# jmb575.net
KiCad netlist of a schematic drawn in Altium Designer
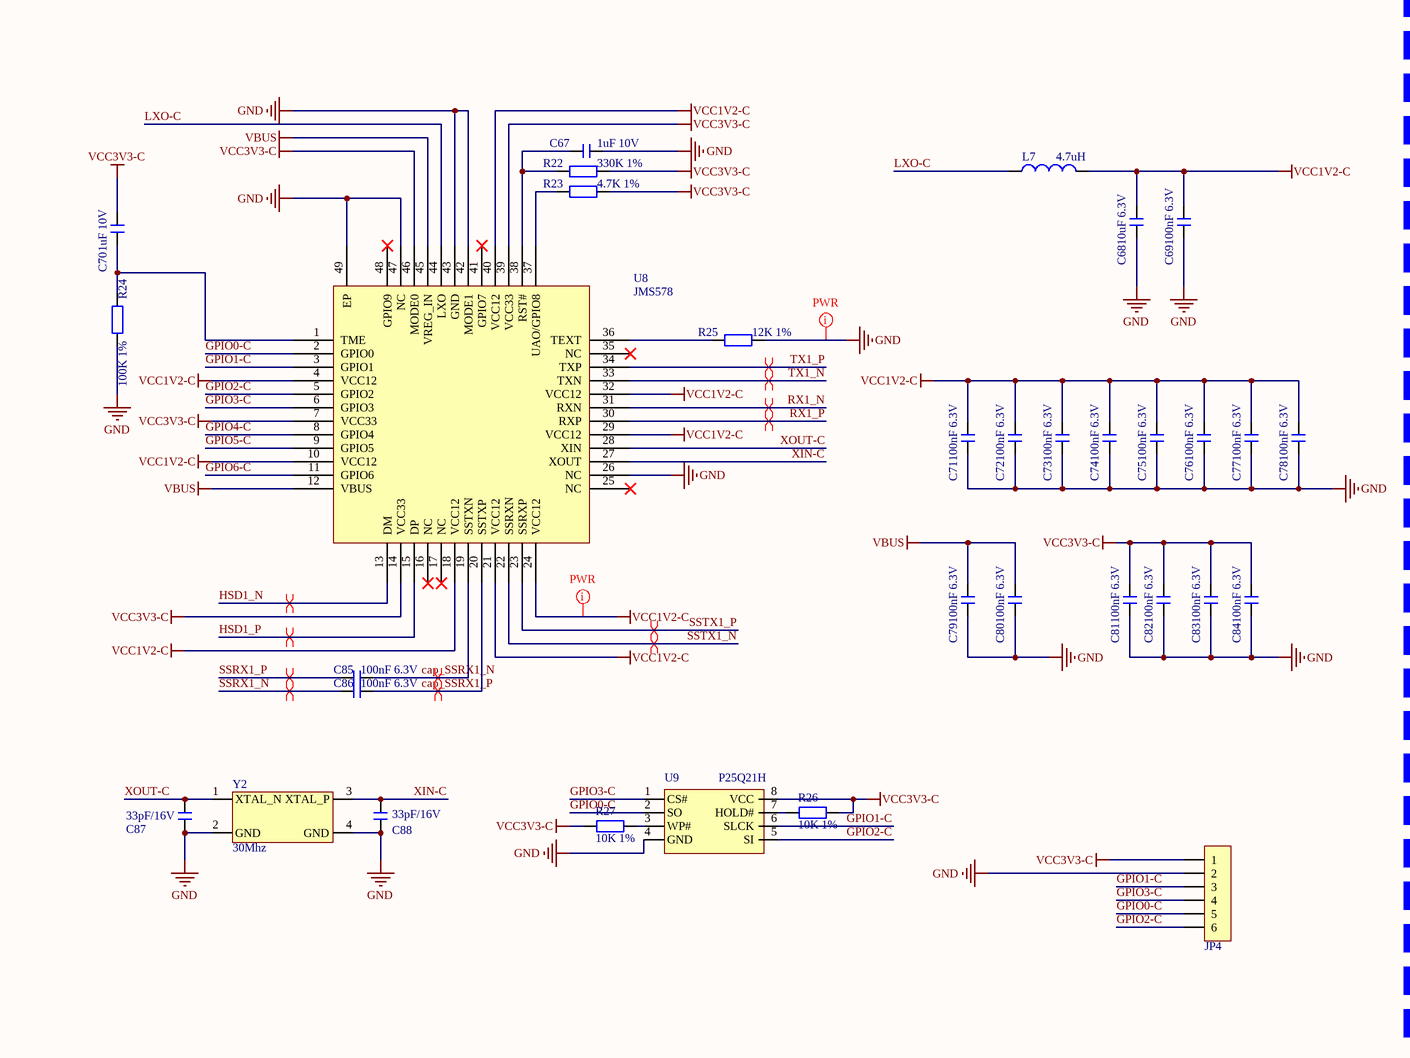
[diagram p0: jmb575.SchDoc, left]
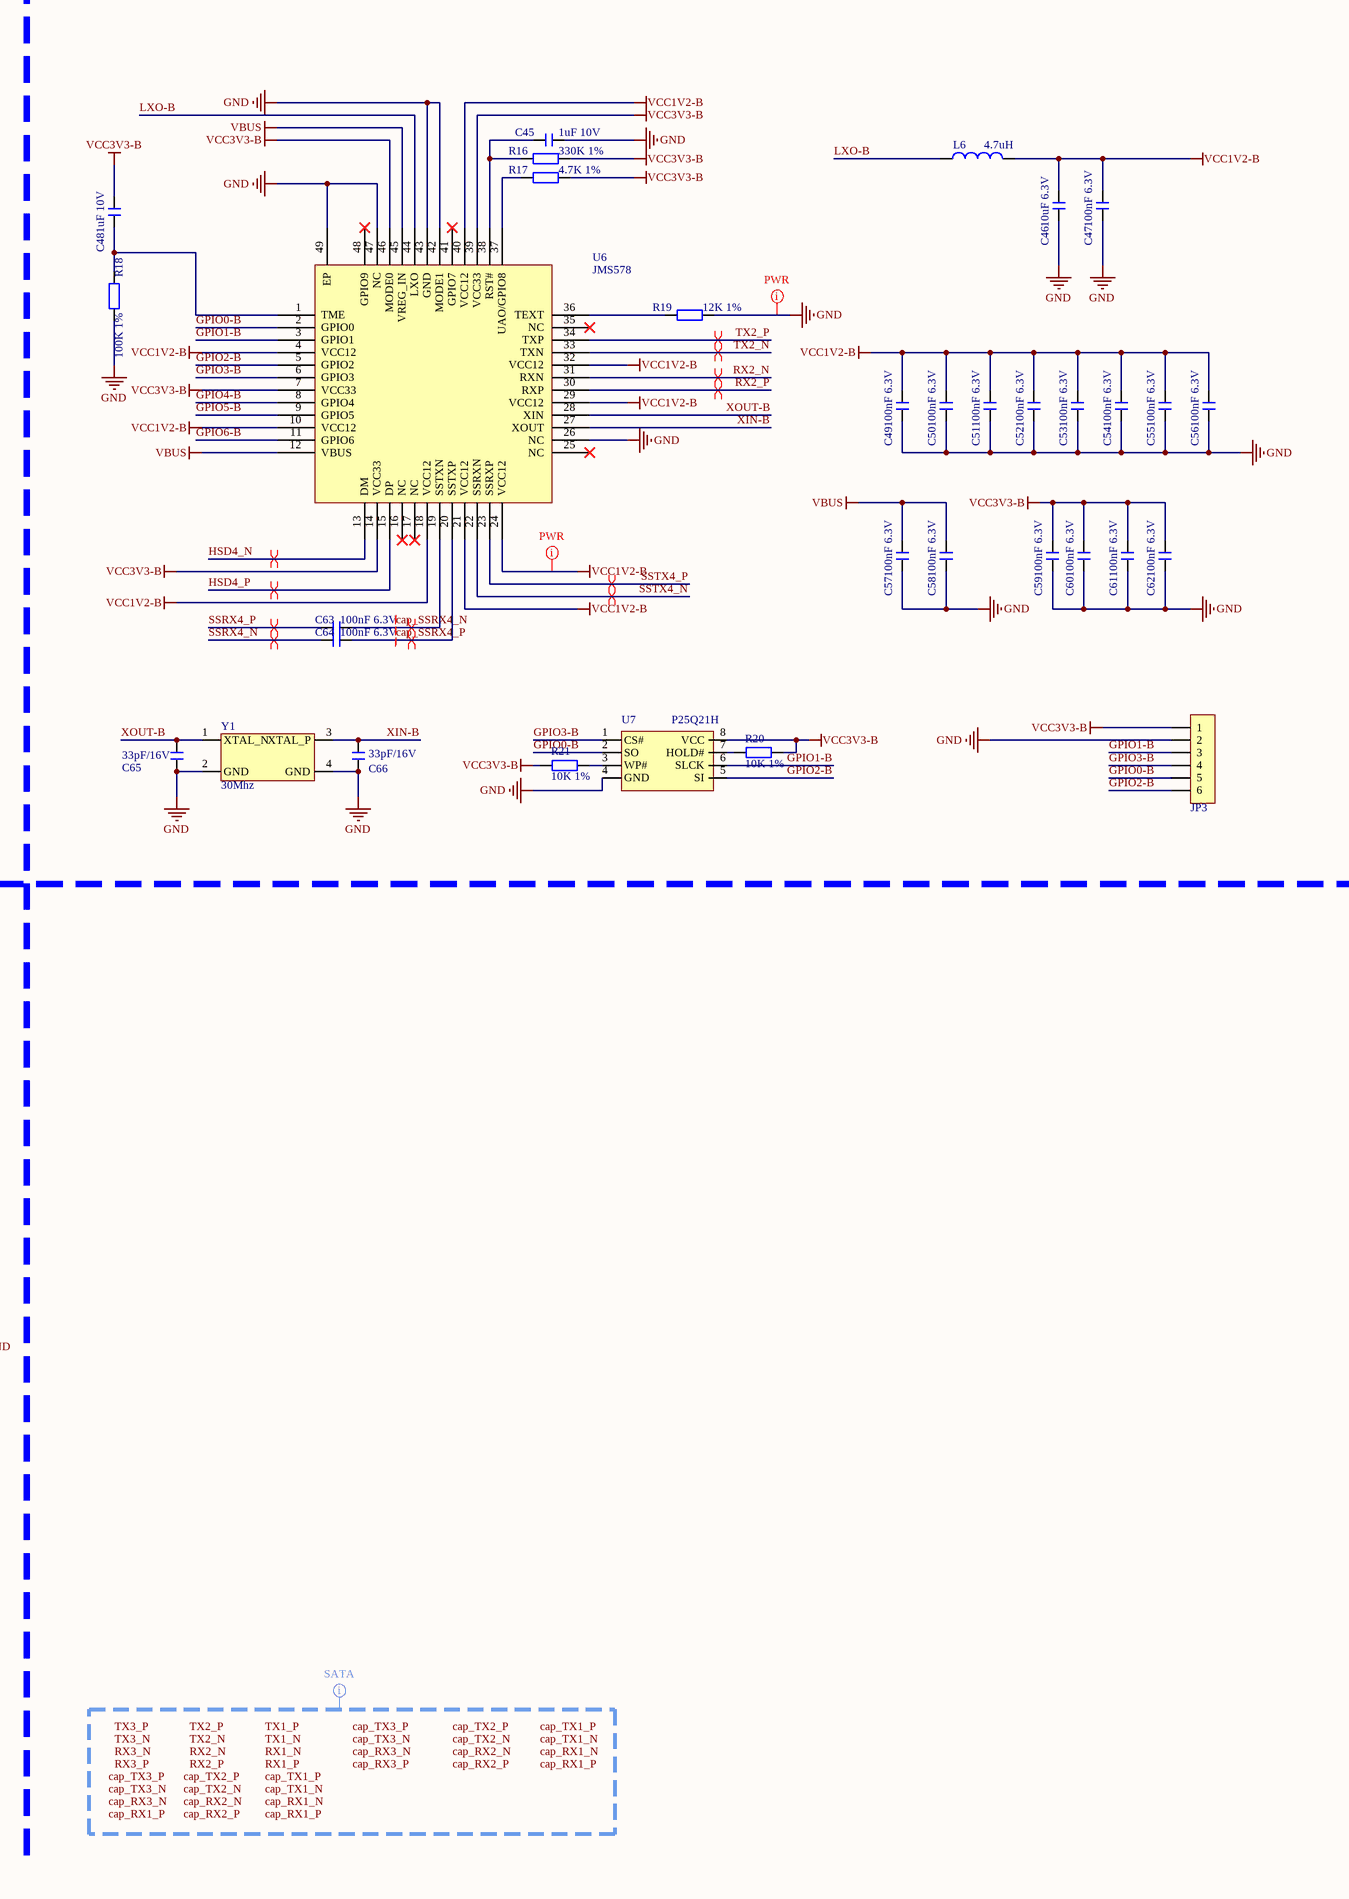
[diagram p1: jmb575.SchDoc, right]

(export (version "E")
  (design (tool "Eeschema 10.0.6"))
  (components
    (comp (ref "C45")
      (value "1uF 10V")
      (footprint "C0402_L")
      (description "无极性贴片电容")
      (fields (field (name "版权归属") "源创客"))
      (libsource (lib "Capacitor") (part "C"))
    )
    (comp (ref "C46")
      (value "10uF 6.3V")
      (footprint "C0603_L")
      (description "无极性贴片电容")
      (fields (field (name "版权归属") "源创客"))
      (libsource (lib "Capacitor") (part "C"))
    )
    (comp (ref "C47")
      (value "100nF 6.3V")
      (footprint "C0402_L")
      (description "无极性贴片电容")
      (fields (field (name "版权归属") "源创客"))
      (libsource (lib "Capacitor") (part "C"))
    )
    (comp (ref "C48")
      (value "1uF 10V")
      (footprint "C0402_L")
      (description "无极性贴片电容")
      (fields (field (name "版权归属") "源创客"))
      (libsource (lib "Capacitor") (part "C"))
    )
    (comp (ref "C49")
      (value "100nF 6.3V")
      (footprint "C0402_L")
      (description "无极性贴片电容")
      (fields (field (name "版权归属") "源创客"))
      (libsource (lib "Capacitor") (part "C"))
    )
    (comp (ref "C50")
      (value "100nF 6.3V")
      (footprint "C0402_L")
      (description "无极性贴片电容")
      (fields (field (name "版权归属") "源创客"))
      (libsource (lib "Capacitor") (part "C"))
    )
    (comp (ref "C51")
      (value "100nF 6.3V")
      (footprint "C0402_L")
      (description "无极性贴片电容")
      (fields (field (name "版权归属") "源创客"))
      (libsource (lib "Capacitor") (part "C"))
    )
    (comp (ref "C52")
      (value "100nF 6.3V")
      (footprint "C0402_L")
      (description "无极性贴片电容")
      (fields (field (name "版权归属") "源创客"))
      (libsource (lib "Capacitor") (part "C"))
    )
    (comp (ref "C53")
      (value "100nF 6.3V")
      (footprint "C0402_L")
      (description "无极性贴片电容")
      (fields (field (name "版权归属") "源创客"))
      (libsource (lib "Capacitor") (part "C"))
    )
    (comp (ref "C54")
      (value "100nF 6.3V")
      (footprint "C0402_L")
      (description "无极性贴片电容")
      (fields (field (name "版权归属") "源创客"))
      (libsource (lib "Capacitor") (part "C"))
    )
    (comp (ref "C55")
      (value "100nF 6.3V")
      (footprint "C0402_L")
      (description "无极性贴片电容")
      (fields (field (name "版权归属") "源创客"))
      (libsource (lib "Capacitor") (part "C"))
    )
    (comp (ref "C56")
      (value "100nF 6.3V")
      (footprint "C0402_L")
      (description "无极性贴片电容")
      (fields (field (name "版权归属") "源创客"))
      (libsource (lib "Capacitor") (part "C"))
    )
    (comp (ref "C57")
      (value "100nF 6.3V")
      (footprint "C0402_L")
      (description "无极性贴片电容")
      (fields (field (name "版权归属") "源创客"))
      (libsource (lib "Capacitor") (part "C"))
    )
    (comp (ref "C58")
      (value "100nF 6.3V")
      (footprint "C0402_L")
      (description "无极性贴片电容")
      (fields (field (name "版权归属") "源创客"))
      (libsource (lib "Capacitor") (part "C"))
    )
    (comp (ref "C59")
      (value "100nF 6.3V")
      (footprint "C0402_L")
      (description "无极性贴片电容")
      (fields (field (name "版权归属") "源创客"))
      (libsource (lib "Capacitor") (part "C"))
    )
    (comp (ref "C60")
      (value "100nF 6.3V")
      (footprint "C0402_L")
      (description "无极性贴片电容")
      (fields (field (name "版权归属") "源创客"))
      (libsource (lib "Capacitor") (part "C"))
    )
    (comp (ref "C61")
      (value "100nF 6.3V")
      (footprint "C0402_L")
      (description "无极性贴片电容")
      (fields (field (name "版权归属") "源创客"))
      (libsource (lib "Capacitor") (part "C"))
    )
    (comp (ref "C62")
      (value "100nF 6.3V")
      (footprint "C0402_L")
      (description "无极性贴片电容")
      (fields (field (name "版权归属") "源创客"))
      (libsource (lib "Capacitor") (part "C"))
    )
    (comp (ref "C63")
      (value "100nF 6.3V")
      (footprint "C0402_L")
      (description "无极性贴片电容")
      (fields (field (name "版权归属") "源创客"))
      (libsource (lib "Capacitor") (part "C"))
    )
    (comp (ref "C64")
      (value "100nF 6.3V")
      (footprint "C0402_L")
      (description "无极性贴片电容")
      (fields (field (name "版权归属") "源创客"))
      (libsource (lib "Capacitor") (part "C"))
    )
    (comp (ref "C65")
      (value "33pF/16V")
      (footprint "C0402_L")
      (description "无极性贴片电容")
      (fields (field (name "版权归属") "源创客"))
      (libsource (lib "Capacitor") (part "C"))
    )
    (comp (ref "C66")
      (value "33pF/16V")
      (footprint "C0402_L")
      (description "无极性贴片电容")
      (fields (field (name "版权归属") "源创客"))
      (libsource (lib "Capacitor") (part "C"))
    )
    (comp (ref "C67")
      (value "1uF 10V")
      (footprint "C0402_L")
      (description "无极性贴片电容")
      (fields (field (name "版权归属") "源创客"))
      (libsource (lib "Capacitor") (part "C"))
    )
    (comp (ref "C68")
      (value "10uF 6.3V")
      (footprint "C0603_L")
      (description "无极性贴片电容")
      (fields (field (name "版权归属") "源创客"))
      (libsource (lib "Capacitor") (part "C"))
    )
    (comp (ref "C69")
      (value "100nF 6.3V")
      (footprint "C0402_L")
      (description "无极性贴片电容")
      (fields (field (name "版权归属") "源创客"))
      (libsource (lib "Capacitor") (part "C"))
    )
    (comp (ref "C70")
      (value "1uF 10V")
      (footprint "C0402_L")
      (description "无极性贴片电容")
      (fields (field (name "版权归属") "源创客"))
      (libsource (lib "Capacitor") (part "C"))
    )
    (comp (ref "C71")
      (value "100nF 6.3V")
      (footprint "C0402_L")
      (description "无极性贴片电容")
      (fields (field (name "版权归属") "源创客"))
      (libsource (lib "Capacitor") (part "C"))
    )
    (comp (ref "C72")
      (value "100nF 6.3V")
      (footprint "C0402_L")
      (description "无极性贴片电容")
      (fields (field (name "版权归属") "源创客"))
      (libsource (lib "Capacitor") (part "C"))
    )
    (comp (ref "C73")
      (value "100nF 6.3V")
      (footprint "C0402_L")
      (description "无极性贴片电容")
      (fields (field (name "版权归属") "源创客"))
      (libsource (lib "Capacitor") (part "C"))
    )
    (comp (ref "C74")
      (value "100nF 6.3V")
      (footprint "C0402_L")
      (description "无极性贴片电容")
      (fields (field (name "版权归属") "源创客"))
      (libsource (lib "Capacitor") (part "C"))
    )
    (comp (ref "C75")
      (value "100nF 6.3V")
      (footprint "C0402_L")
      (description "无极性贴片电容")
      (fields (field (name "版权归属") "源创客"))
      (libsource (lib "Capacitor") (part "C"))
    )
    (comp (ref "C76")
      (value "100nF 6.3V")
      (footprint "C0402_L")
      (description "无极性贴片电容")
      (fields (field (name "版权归属") "源创客"))
      (libsource (lib "Capacitor") (part "C"))
    )
    (comp (ref "C77")
      (value "100nF 6.3V")
      (footprint "C0402_L")
      (description "无极性贴片电容")
      (fields (field (name "版权归属") "源创客"))
      (libsource (lib "Capacitor") (part "C"))
    )
    (comp (ref "C78")
      (value "100nF 6.3V")
      (footprint "C0402_L")
      (description "无极性贴片电容")
      (fields (field (name "版权归属") "源创客"))
      (libsource (lib "Capacitor") (part "C"))
    )
    (comp (ref "C79")
      (value "100nF 6.3V")
      (footprint "C0402_L")
      (description "无极性贴片电容")
      (fields (field (name "版权归属") "源创客"))
      (libsource (lib "Capacitor") (part "C"))
    )
    (comp (ref "C80")
      (value "100nF 6.3V")
      (footprint "C0402_L")
      (description "无极性贴片电容")
      (fields (field (name "版权归属") "源创客"))
      (libsource (lib "Capacitor") (part "C"))
    )
    (comp (ref "C81")
      (value "100nF 6.3V")
      (footprint "C0402_L")
      (description "无极性贴片电容")
      (fields (field (name "版权归属") "源创客"))
      (libsource (lib "Capacitor") (part "C"))
    )
    (comp (ref "C82")
      (value "100nF 6.3V")
      (footprint "C0402_L")
      (description "无极性贴片电容")
      (fields (field (name "版权归属") "源创客"))
      (libsource (lib "Capacitor") (part "C"))
    )
    (comp (ref "C83")
      (value "100nF 6.3V")
      (footprint "C0402_L")
      (description "无极性贴片电容")
      (fields (field (name "版权归属") "源创客"))
      (libsource (lib "Capacitor") (part "C"))
    )
    (comp (ref "C84")
      (value "100nF 6.3V")
      (footprint "C0402_L")
      (description "无极性贴片电容")
      (fields (field (name "版权归属") "源创客"))
      (libsource (lib "Capacitor") (part "C"))
    )
    (comp (ref "C85")
      (value "100nF 6.3V")
      (footprint "C0402_L")
      (description "无极性贴片电容")
      (fields (field (name "版权归属") "源创客"))
      (libsource (lib "Capacitor") (part "C"))
    )
    (comp (ref "C86")
      (value "100nF 6.3V")
      (footprint "C0402_L")
      (description "无极性贴片电容")
      (fields (field (name "版权归属") "源创客"))
      (libsource (lib "Capacitor") (part "C"))
    )
    (comp (ref "C87")
      (value "33pF/16V")
      (footprint "C0402_L")
      (description "无极性贴片电容")
      (fields (field (name "版权归属") "源创客"))
      (libsource (lib "Capacitor") (part "C"))
    )
    (comp (ref "C88")
      (value "33pF/16V")
      (footprint "C0402_L")
      (description "无极性贴片电容")
      (fields (field (name "版权归属") "源创客"))
      (libsource (lib "Capacitor") (part "C"))
    )
    (comp (ref "JP3")
      (value "HDR-1X6")
      (footprint "6p烧录点")
      (description "6P接插件")
      (fields (field (name "版权归属") "源创客"))
      (libsource (lib "Connector-PinHeader") (part "Header 6"))
    )
    (comp (ref "JP4")
      (value "HDR-1X6")
      (footprint "6p烧录点")
      (description "6P接插件")
      (fields (field (name "版权归属") "源创客"))
      (libsource (lib "Connector-PinHeader") (part "Header 6"))
    )
    (comp (ref "L6")
      (value "4.7uH")
      (footprint "SMMS0420")
      (description "小功率贴片电感")
      (fields (field (name "版权归属") "源创客"))
      (libsource (lib "Inductor") (part "L"))
    )
    (comp (ref "L7")
      (value "4.7uH")
      (footprint "SMMS0420")
      (description "小功率贴片电感")
      (fields (field (name "版权归属") "源创客"))
      (libsource (lib "Inductor") (part "L"))
    )
    (comp (ref "R16")
      (value "330K 1%")
      (footprint "R0402_L")
      (description "贴片电阻")
      (fields (field (name "版权归属") "源创客"))
      (libsource (lib "Resistor") (part "R"))
    )
    (comp (ref "R17")
      (value "4.7K 1%")
      (footprint "R0402_L")
      (description "贴片电阻")
      (fields (field (name "版权归属") "源创客"))
      (libsource (lib "Resistor") (part "R"))
    )
    (comp (ref "R18")
      (value "100K 1%")
      (footprint "R0402_L")
      (description "贴片电阻")
      (fields (field (name "版权归属") "源创客"))
      (libsource (lib "Resistor") (part "R"))
    )
    (comp (ref "R19")
      (value "12K 1%")
      (footprint "R0402_L")
      (description "贴片电阻")
      (fields (field (name "版权归属") "源创客"))
      (libsource (lib "Resistor") (part "R"))
    )
    (comp (ref "R20")
      (value "10K 1%")
      (footprint "R0402_L")
      (description "贴片电阻")
      (fields (field (name "版权归属") "源创客"))
      (libsource (lib "Resistor") (part "R"))
    )
    (comp (ref "R21")
      (value "10K 1%")
      (footprint "R0402_L")
      (description "贴片电阻")
      (fields (field (name "版权归属") "源创客"))
      (libsource (lib "Resistor") (part "R"))
    )
    (comp (ref "R22")
      (value "330K 1%")
      (footprint "R0402_L")
      (description "贴片电阻")
      (fields (field (name "版权归属") "源创客"))
      (libsource (lib "Resistor") (part "R"))
    )
    (comp (ref "R23")
      (value "4.7K 1%")
      (footprint "R0402_L")
      (description "贴片电阻")
      (fields (field (name "版权归属") "源创客"))
      (libsource (lib "Resistor") (part "R"))
    )
    (comp (ref "R24")
      (value "100K 1%")
      (footprint "R0402_L")
      (description "贴片电阻")
      (fields (field (name "版权归属") "源创客"))
      (libsource (lib "Resistor") (part "R"))
    )
    (comp (ref "R25")
      (value "12K 1%")
      (footprint "R0402_L")
      (description "贴片电阻")
      (fields (field (name "版权归属") "源创客"))
      (libsource (lib "Resistor") (part "R"))
    )
    (comp (ref "R26")
      (value "10K 1%")
      (footprint "R0402_L")
      (description "贴片电阻")
      (fields (field (name "版权归属") "源创客"))
      (libsource (lib "Resistor") (part "R"))
    )
    (comp (ref "R27")
      (value "10K 1%")
      (footprint "R0402_L")
      (description "贴片电阻")
      (fields (field (name "版权归属") "源创客"))
      (libsource (lib "Resistor") (part "R"))
    )
    (comp (ref "U6")
      (value "JMS578")
      (footprint "QFN48-L6.0-W6.0-P0.4")
      (libsource (lib "Brage") (part "JMS578"))
    )
    (comp (ref "U7") (value "P25Q21H") (footprint "SOP8_L") (libsource (lib "Flash") (part "P25D40H")))
    (comp (ref "U8")
      (value "JMS578")
      (footprint "QFN48-L6.0-W6.0-P0.4")
      (libsource (lib "Brage") (part "JMS578"))
    )
    (comp (ref "U9") (value "P25Q21H") (footprint "SOP8_L") (libsource (lib "Flash") (part "P25D40H")))
    (comp (ref "Y1") (value "30Mhz") (footprint "OSC 3225-4P") (libsource (lib "Crystal") (part "Crystal")))
    (comp (ref "Y2") (value "30Mhz") (footprint "OSC 3225-4P") (libsource (lib "Crystal") (part "Crystal")))
  )
  (nets
    (net (code "1") (name "/GPIO0-B") (class "Default")
      (node (ref "JP3") (pin "5") (pinfunction "5_5") (pintype "passive"))
      (node (ref "U6") (pin "2") (pinfunction "GPIO0_2") (pintype "passive"))
      (node (ref "U7") (pin "2") (pinfunction "SO_2") (pintype "passive"))
    )
    (net (code "2") (name "/GPIO0-C") (class "Default")
      (node (ref "JP4") (pin "5") (pinfunction "5_5") (pintype "passive"))
      (node (ref "U8") (pin "2") (pinfunction "GPIO0_2") (pintype "passive"))
      (node (ref "U9") (pin "2") (pinfunction "SO_2") (pintype "passive"))
    )
    (net (code "3") (name "/GPIO1-B") (class "Default")
      (node (ref "JP3") (pin "3") (pinfunction "3_3") (pintype "passive"))
      (node (ref "U6") (pin "3") (pinfunction "GPIO1_3") (pintype "passive"))
      (node (ref "U7") (pin "6") (pinfunction "SLCK_6") (pintype "passive"))
    )
    (net (code "4") (name "/GPIO1-C") (class "Default")
      (node (ref "JP4") (pin "3") (pinfunction "3_3") (pintype "passive"))
      (node (ref "U8") (pin "3") (pinfunction "GPIO1_3") (pintype "passive"))
      (node (ref "U9") (pin "6") (pinfunction "SLCK_6") (pintype "passive"))
    )
    (net (code "5") (name "/GPIO2-B") (class "Default")
      (node (ref "JP3") (pin "6") (pinfunction "6_6") (pintype "passive"))
      (node (ref "U6") (pin "5") (pinfunction "GPIO2_5") (pintype "passive"))
      (node (ref "U7") (pin "5") (pinfunction "SI_5") (pintype "passive"))
    )
    (net (code "6") (name "/GPIO2-C") (class "Default")
      (node (ref "JP4") (pin "6") (pinfunction "6_6") (pintype "passive"))
      (node (ref "U8") (pin "5") (pinfunction "GPIO2_5") (pintype "passive"))
      (node (ref "U9") (pin "5") (pinfunction "SI_5") (pintype "passive"))
    )
    (net (code "7") (name "/GPIO3-B") (class "Default")
      (node (ref "JP3") (pin "4") (pinfunction "4_4") (pintype "passive"))
      (node (ref "U6") (pin "6") (pinfunction "GPIO3_6") (pintype "passive"))
      (node (ref "U7") (pin "1") (pinfunction "CS#_1") (pintype "passive"))
    )
    (net (code "8") (name "/GPIO3-C") (class "Default")
      (node (ref "JP4") (pin "4") (pinfunction "4_4") (pintype "passive"))
      (node (ref "U8") (pin "6") (pinfunction "GPIO3_6") (pintype "passive"))
      (node (ref "U9") (pin "1") (pinfunction "CS#_1") (pintype "passive"))
    )
    (net (code "9") (name "/GPIO4-B") (class "Default")
      (node (ref "U6") (pin "8") (pinfunction "GPIO4_8") (pintype "passive"))
    )
    (net (code "10") (name "/GPIO4-C") (class "Default")
      (node (ref "U8") (pin "8") (pinfunction "GPIO4_8") (pintype "passive"))
    )
    (net (code "11") (name "/GPIO5-B") (class "Default")
      (node (ref "U6") (pin "9") (pinfunction "GPIO5_9") (pintype "passive"))
    )
    (net (code "12") (name "/GPIO5-C") (class "Default")
      (node (ref "U8") (pin "9") (pinfunction "GPIO5_9") (pintype "passive"))
    )
    (net (code "13") (name "/GPIO6-B") (class "Default")
      (node (ref "U6") (pin "11") (pinfunction "GPIO6_11") (pintype "passive"))
    )
    (net (code "14") (name "/GPIO6-C") (class "Default")
      (node (ref "U8") (pin "11") (pinfunction "GPIO6_11") (pintype "passive"))
    )
    (net (code "15") (name "/HSD1_N") (class "Default")
      (node (ref "U8") (pin "13") (pinfunction "DM_13") (pintype "passive"))
    )
    (net (code "16") (name "/HSD1_P") (class "Default")
      (node (ref "U8") (pin "15") (pinfunction "DP_15") (pintype "passive"))
    )
    (net (code "17") (name "/HSD4_N") (class "Default")
      (node (ref "U6") (pin "13") (pinfunction "DM_13") (pintype "passive"))
    )
    (net (code "18") (name "/HSD4_P") (class "Default")
      (node (ref "U6") (pin "15") (pinfunction "DP_15") (pintype "passive"))
    )
    (net (code "19") (name "/LXO-B") (class "Default")
      (node (ref "L6") (pin "1") (pinfunction "1_1") (pintype "passive"))
      (node (ref "U6") (pin "44") (pinfunction "LXO_44") (pintype "passive"))
    )
    (net (code "20") (name "/LXO-C") (class "Default")
      (node (ref "L7") (pin "1") (pinfunction "1_1") (pintype "passive"))
      (node (ref "U8") (pin "44") (pinfunction "LXO_44") (pintype "passive"))
    )
    (net (code "21") (name "/RX1_N") (class "Default")
      (node (ref "U8") (pin "31") (pinfunction "RXN_31") (pintype "passive"))
    )
    (net (code "22") (name "/RX1_P") (class "Default")
      (node (ref "U8") (pin "30") (pinfunction "RXP_30") (pintype "passive"))
    )
    (net (code "23") (name "/RX2_N") (class "Default")
      (node (ref "U6") (pin "31") (pinfunction "RXN_31") (pintype "passive"))
    )
    (net (code "24") (name "/RX2_P") (class "Default")
      (node (ref "U6") (pin "30") (pinfunction "RXP_30") (pintype "passive"))
    )
    (net (code "27") (name "/SSRX1_N") (class "Default")
      (node (ref "C86") (pin "1") (pinfunction "1_1") (pintype "passive"))
    )
    (net (code "28") (name "/SSRX1_P") (class "Default")
      (node (ref "C85") (pin "1") (pinfunction "1_1") (pintype "passive"))
    )
    (net (code "29") (name "/SSRX4_N") (class "Default")
      (node (ref "C64") (pin "1") (pinfunction "1_1") (pintype "passive"))
    )
    (net (code "30") (name "/SSRX4_P") (class "Default")
      (node (ref "C63") (pin "1") (pinfunction "1_1") (pintype "passive"))
    )
    (net (code "31") (name "/SSTX1_N") (class "Default")
      (node (ref "U8") (pin "22") (pinfunction "SSRXN_22") (pintype "passive"))
    )
    (net (code "32") (name "/SSTX1_P") (class "Default")
      (node (ref "U8") (pin "23") (pinfunction "SSRXP_23") (pintype "passive"))
    )
    (net (code "33") (name "/SSTX4_N") (class "Default")
      (node (ref "U6") (pin "22") (pinfunction "SSRXN_22") (pintype "passive"))
    )
    (net (code "34") (name "/SSTX4_P") (class "Default")
      (node (ref "U6") (pin "23") (pinfunction "SSRXP_23") (pintype "passive"))
    )
    (net (code "35") (name "/TX1_N") (class "Default")
      (node (ref "U8") (pin "33") (pinfunction "TXN_33") (pintype "passive"))
    )
    (net (code "36") (name "/TX1_P") (class "Default")
      (node (ref "U8") (pin "34") (pinfunction "TXP_34") (pintype "passive"))
    )
    (net (code "37") (name "/TX2_N") (class "Default")
      (node (ref "U6") (pin "33") (pinfunction "TXN_33") (pintype "passive"))
    )
    (net (code "38") (name "/TX2_P") (class "Default")
      (node (ref "U6") (pin "34") (pinfunction "TXP_34") (pintype "passive"))
    )
    (net (code "41") (name "/XIN-B") (class "Default")
      (node (ref "C66") (pin "1") (pinfunction "1_1") (pintype "passive"))
      (node (ref "U6") (pin "27") (pinfunction "XOUT_27") (pintype "passive"))
      (node (ref "Y1") (pin "3") (pinfunction "XTAL_P_3") (pintype "passive"))
    )
    (net (code "42") (name "/XIN-C") (class "Default")
      (node (ref "C88") (pin "1") (pinfunction "1_1") (pintype "passive"))
      (node (ref "U8") (pin "27") (pinfunction "XOUT_27") (pintype "passive"))
      (node (ref "Y2") (pin "3") (pinfunction "XTAL_P_3") (pintype "passive"))
    )
    (net (code "43") (name "/XOUT-B") (class "Default")
      (node (ref "C65") (pin "1") (pinfunction "1_1") (pintype "passive"))
      (node (ref "U6") (pin "28") (pinfunction "XIN_28") (pintype "passive"))
      (node (ref "Y1") (pin "1") (pinfunction "XTAL_N_1") (pintype "passive"))
    )
    (net (code "44") (name "/XOUT-C") (class "Default")
      (node (ref "C87") (pin "1") (pinfunction "1_1") (pintype "passive"))
      (node (ref "U8") (pin "28") (pinfunction "XIN_28") (pintype "passive"))
      (node (ref "Y2") (pin "1") (pinfunction "XTAL_N_1") (pintype "passive"))
    )
    (net (code "51") (name "/cap_SSRX1_N") (class "Default")
      (node (ref "C85") (pin "2") (pinfunction "2_2") (pintype "passive"))
      (node (ref "U8") (pin "19") (pinfunction "SSTXN_19") (pintype "passive"))
    )
    (net (code "52") (name "/cap_SSRX1_P") (class "Default")
      (node (ref "C86") (pin "2") (pinfunction "2_2") (pintype "passive"))
      (node (ref "U8") (pin "20") (pinfunction "SSTXP_20") (pintype "passive"))
    )
    (net (code "53") (name "/cap_SSRX4_N") (class "Default")
      (node (ref "C63") (pin "2") (pinfunction "2_2") (pintype "passive"))
      (node (ref "U6") (pin "19") (pinfunction "SSTXN_19") (pintype "passive"))
    )
    (net (code "54") (name "/cap_SSRX4_P") (class "Default")
      (node (ref "C64") (pin "2") (pinfunction "2_2") (pintype "passive"))
      (node (ref "U6") (pin "20") (pinfunction "SSTXP_20") (pintype "passive"))
    )
    (net (code "61") (name "GND") (class "Default")
      (node (ref "C45") (pin "1") (pinfunction "1_1") (pintype "passive"))
      (node (ref "C46") (pin "1") (pinfunction "1_1") (pintype "passive"))
      (node (ref "C47") (pin "1") (pinfunction "1_1") (pintype "passive"))
      (node (ref "C49") (pin "1") (pinfunction "1_1") (pintype "passive"))
      (node (ref "C50") (pin "1") (pinfunction "1_1") (pintype "passive"))
      (node (ref "C51") (pin "1") (pinfunction "1_1") (pintype "passive"))
      (node (ref "C52") (pin "1") (pinfunction "1_1") (pintype "passive"))
      (node (ref "C53") (pin "1") (pinfunction "1_1") (pintype "passive"))
      (node (ref "C54") (pin "1") (pinfunction "1_1") (pintype "passive"))
      (node (ref "C55") (pin "1") (pinfunction "1_1") (pintype "passive"))
      (node (ref "C56") (pin "1") (pinfunction "1_1") (pintype "passive"))
      (node (ref "C57") (pin "1") (pinfunction "1_1") (pintype "passive"))
      (node (ref "C58") (pin "1") (pinfunction "1_1") (pintype "passive"))
      (node (ref "C59") (pin "1") (pinfunction "1_1") (pintype "passive"))
      (node (ref "C60") (pin "1") (pinfunction "1_1") (pintype "passive"))
      (node (ref "C61") (pin "1") (pinfunction "1_1") (pintype "passive"))
      (node (ref "C62") (pin "1") (pinfunction "1_1") (pintype "passive"))
      (node (ref "C65") (pin "2") (pinfunction "2_2") (pintype "passive"))
      (node (ref "C66") (pin "2") (pinfunction "2_2") (pintype "passive"))
      (node (ref "C67") (pin "1") (pinfunction "1_1") (pintype "passive"))
      (node (ref "C68") (pin "1") (pinfunction "1_1") (pintype "passive"))
      (node (ref "C69") (pin "1") (pinfunction "1_1") (pintype "passive"))
      (node (ref "C71") (pin "1") (pinfunction "1_1") (pintype "passive"))
      (node (ref "C72") (pin "1") (pinfunction "1_1") (pintype "passive"))
      (node (ref "C73") (pin "1") (pinfunction "1_1") (pintype "passive"))
      (node (ref "C74") (pin "1") (pinfunction "1_1") (pintype "passive"))
      (node (ref "C75") (pin "1") (pinfunction "1_1") (pintype "passive"))
      (node (ref "C76") (pin "1") (pinfunction "1_1") (pintype "passive"))
      (node (ref "C77") (pin "1") (pinfunction "1_1") (pintype "passive"))
      (node (ref "C78") (pin "1") (pinfunction "1_1") (pintype "passive"))
      (node (ref "C79") (pin "1") (pinfunction "1_1") (pintype "passive"))
      (node (ref "C80") (pin "1") (pinfunction "1_1") (pintype "passive"))
      (node (ref "C81") (pin "1") (pinfunction "1_1") (pintype "passive"))
      (node (ref "C82") (pin "1") (pinfunction "1_1") (pintype "passive"))
      (node (ref "C83") (pin "1") (pinfunction "1_1") (pintype "passive"))
      (node (ref "C84") (pin "1") (pinfunction "1_1") (pintype "passive"))
      (node (ref "C87") (pin "2") (pinfunction "2_2") (pintype "passive"))
      (node (ref "C88") (pin "2") (pinfunction "2_2") (pintype "passive"))
      (node (ref "JP3") (pin "2") (pinfunction "2_2") (pintype "passive"))
      (node (ref "JP4") (pin "2") (pinfunction "2_2") (pintype "passive"))
      (node (ref "R18") (pin "1") (pinfunction "1_1") (pintype "passive"))
      (node (ref "R19") (pin "1") (pinfunction "1_1") (pintype "passive"))
      (node (ref "R24") (pin "1") (pinfunction "1_1") (pintype "passive"))
      (node (ref "R25") (pin "1") (pinfunction "1_1") (pintype "passive"))
      (node (ref "U6") (pin "26") (pinfunction "NC_26") (pintype "passive"))
      (node (ref "U6") (pin "42") (pinfunction "MODE1_42") (pintype "passive"))
      (node (ref "U6") (pin "43") (pinfunction "GND_43") (pintype "passive"))
      (node (ref "U6") (pin "47") (pinfunction "NC_47") (pintype "passive"))
      (node (ref "U6") (pin "49") (pinfunction "EP_49") (pintype "passive"))
      (node (ref "U7") (pin "4") (pinfunction "GND_4") (pintype "passive"))
      (node (ref "U8") (pin "26") (pinfunction "NC_26") (pintype "passive"))
      (node (ref "U8") (pin "42") (pinfunction "MODE1_42") (pintype "passive"))
      (node (ref "U8") (pin "43") (pinfunction "GND_43") (pintype "passive"))
      (node (ref "U8") (pin "47") (pinfunction "NC_47") (pintype "passive"))
      (node (ref "U8") (pin "49") (pinfunction "EP_49") (pintype "passive"))
      (node (ref "U9") (pin "4") (pinfunction "GND_4") (pintype "passive"))
      (node (ref "Y1") (pin "2") (pinfunction "GND_2") (pintype "passive"))
      (node (ref "Y1") (pin "4") (pinfunction "GND_4") (pintype "passive"))
      (node (ref "Y2") (pin "2") (pinfunction "GND_2") (pintype "passive"))
      (node (ref "Y2") (pin "4") (pinfunction "GND_4") (pintype "passive"))
    )
    (net (code "62") (name "Net-(U6-RST#)") (class "Default")
      (node (ref "C45") (pin "2") (pinfunction "2_2") (pintype "passive"))
      (node (ref "R16") (pin "2") (pinfunction "2_2") (pintype "passive"))
      (node (ref "U6") (pin "38") (pinfunction "RST#_38") (pintype "passive"))
    )
    (net (code "63") (name "Net-(U6-TEXT)") (class "Default")
      (node (ref "R19") (pin "2") (pinfunction "2_2") (pintype "passive"))
      (node (ref "U6") (pin "36") (pinfunction "TEXT_36") (pintype "passive"))
    )
    (net (code "64") (name "Net-(U6-TME)") (class "Default")
      (node (ref "C48") (pin "1") (pinfunction "1_1") (pintype "passive"))
      (node (ref "R18") (pin "2") (pinfunction "2_2") (pintype "passive"))
      (node (ref "U6") (pin "1") (pinfunction "TME_1") (pintype "passive"))
    )
    (net (code "65") (name "Net-(U6-UAO{slash}GPIO8)") (class "Default")
      (node (ref "R17") (pin "2") (pinfunction "2_2") (pintype "passive"))
      (node (ref "U6") (pin "37") (pinfunction "UAO/GPIO8_37") (pintype "passive"))
    )
    (net (code "66") (name "Net-(U7-HOLD#)") (class "Default")
      (node (ref "R20") (pin "2") (pinfunction "2_2") (pintype "passive"))
      (node (ref "U7") (pin "7") (pinfunction "HOLD#_7") (pintype "passive"))
    )
    (net (code "67") (name "Net-(U7-WP#)") (class "Default")
      (node (ref "R21") (pin "2") (pinfunction "2_2") (pintype "passive"))
      (node (ref "U7") (pin "3") (pinfunction "WP#_3") (pintype "passive"))
    )
    (net (code "68") (name "Net-(U8-RST#)") (class "Default")
      (node (ref "C67") (pin "2") (pinfunction "2_2") (pintype "passive"))
      (node (ref "R22") (pin "2") (pinfunction "2_2") (pintype "passive"))
      (node (ref "U8") (pin "38") (pinfunction "RST#_38") (pintype "passive"))
    )
    (net (code "69") (name "Net-(U8-TEXT)") (class "Default")
      (node (ref "R25") (pin "2") (pinfunction "2_2") (pintype "passive"))
      (node (ref "U8") (pin "36") (pinfunction "TEXT_36") (pintype "passive"))
    )
    (net (code "70") (name "Net-(U8-TME)") (class "Default")
      (node (ref "C70") (pin "1") (pinfunction "1_1") (pintype "passive"))
      (node (ref "R24") (pin "2") (pinfunction "2_2") (pintype "passive"))
      (node (ref "U8") (pin "1") (pinfunction "TME_1") (pintype "passive"))
    )
    (net (code "71") (name "Net-(U8-UAO{slash}GPIO8)") (class "Default")
      (node (ref "R23") (pin "2") (pinfunction "2_2") (pintype "passive"))
      (node (ref "U8") (pin "37") (pinfunction "UAO/GPIO8_37") (pintype "passive"))
    )
    (net (code "72") (name "Net-(U9-HOLD#)") (class "Default")
      (node (ref "R26") (pin "2") (pinfunction "2_2") (pintype "passive"))
      (node (ref "U9") (pin "7") (pinfunction "HOLD#_7") (pintype "passive"))
    )
    (net (code "73") (name "Net-(U9-WP#)") (class "Default")
      (node (ref "R27") (pin "1") (pinfunction "1_1") (pintype "passive"))
      (node (ref "U9") (pin "3") (pinfunction "WP#_3") (pintype "passive"))
    )
    (net (code "74") (name "VBUS") (class "Default")
      (node (ref "C57") (pin "2") (pinfunction "2_2") (pintype "passive"))
      (node (ref "C58") (pin "2") (pinfunction "2_2") (pintype "passive"))
      (node (ref "C79") (pin "2") (pinfunction "2_2") (pintype "passive"))
      (node (ref "C80") (pin "2") (pinfunction "2_2") (pintype "passive"))
      (node (ref "U6") (pin "12") (pinfunction "VBUS_12") (pintype "passive"))
      (node (ref "U6") (pin "45") (pinfunction "VREG_IN_45") (pintype "passive"))
      (node (ref "U8") (pin "12") (pinfunction "VBUS_12") (pintype "passive"))
      (node (ref "U8") (pin "45") (pinfunction "VREG_IN_45") (pintype "passive"))
    )
    (net (code "75") (name "VCC1V2-B") (class "Default")
      (node (ref "C46") (pin "2") (pinfunction "2_2") (pintype "passive"))
      (node (ref "C47") (pin "2") (pinfunction "2_2") (pintype "passive"))
      (node (ref "C49") (pin "2") (pinfunction "2_2") (pintype "passive"))
      (node (ref "C50") (pin "2") (pinfunction "2_2") (pintype "passive"))
      (node (ref "C51") (pin "2") (pinfunction "2_2") (pintype "passive"))
      (node (ref "C52") (pin "2") (pinfunction "2_2") (pintype "passive"))
      (node (ref "C53") (pin "2") (pinfunction "2_2") (pintype "passive"))
      (node (ref "C54") (pin "2") (pinfunction "2_2") (pintype "passive"))
      (node (ref "C55") (pin "2") (pinfunction "2_2") (pintype "passive"))
      (node (ref "C56") (pin "2") (pinfunction "2_2") (pintype "passive"))
      (node (ref "L6") (pin "2") (pinfunction "2_2") (pintype "passive"))
      (node (ref "U6") (pin "10") (pinfunction "VCC12_10") (pintype "passive"))
      (node (ref "U6") (pin "18") (pinfunction "VCC12_18") (pintype "passive"))
      (node (ref "U6") (pin "21") (pinfunction "VCC12_21") (pintype "passive"))
      (node (ref "U6") (pin "24") (pinfunction "VCC12_24") (pintype "passive"))
      (node (ref "U6") (pin "29") (pinfunction "VCC12_29") (pintype "passive"))
      (node (ref "U6") (pin "32") (pinfunction "VCC12_32") (pintype "passive"))
      (node (ref "U6") (pin "4") (pinfunction "VCC12_4") (pintype "passive"))
      (node (ref "U6") (pin "40") (pinfunction "VCC12_40") (pintype "passive"))
    )
    (net (code "76") (name "VCC1V2-C") (class "Default")
      (node (ref "C68") (pin "2") (pinfunction "2_2") (pintype "passive"))
      (node (ref "C69") (pin "2") (pinfunction "2_2") (pintype "passive"))
      (node (ref "C71") (pin "2") (pinfunction "2_2") (pintype "passive"))
      (node (ref "C72") (pin "2") (pinfunction "2_2") (pintype "passive"))
      (node (ref "C73") (pin "2") (pinfunction "2_2") (pintype "passive"))
      (node (ref "C74") (pin "2") (pinfunction "2_2") (pintype "passive"))
      (node (ref "C75") (pin "2") (pinfunction "2_2") (pintype "passive"))
      (node (ref "C76") (pin "2") (pinfunction "2_2") (pintype "passive"))
      (node (ref "C77") (pin "2") (pinfunction "2_2") (pintype "passive"))
      (node (ref "C78") (pin "2") (pinfunction "2_2") (pintype "passive"))
      (node (ref "L7") (pin "2") (pinfunction "2_2") (pintype "passive"))
      (node (ref "U8") (pin "10") (pinfunction "VCC12_10") (pintype "passive"))
      (node (ref "U8") (pin "18") (pinfunction "VCC12_18") (pintype "passive"))
      (node (ref "U8") (pin "21") (pinfunction "VCC12_21") (pintype "passive"))
      (node (ref "U8") (pin "24") (pinfunction "VCC12_24") (pintype "passive"))
      (node (ref "U8") (pin "29") (pinfunction "VCC12_29") (pintype "passive"))
      (node (ref "U8") (pin "32") (pinfunction "VCC12_32") (pintype "passive"))
      (node (ref "U8") (pin "4") (pinfunction "VCC12_4") (pintype "passive"))
      (node (ref "U8") (pin "40") (pinfunction "VCC12_40") (pintype "passive"))
    )
    (net (code "77") (name "VCC3V3-B") (class "Default")
      (node (ref "C48") (pin "2") (pinfunction "2_2") (pintype "passive"))
      (node (ref "C59") (pin "2") (pinfunction "2_2") (pintype "passive"))
      (node (ref "C60") (pin "2") (pinfunction "2_2") (pintype "passive"))
      (node (ref "C61") (pin "2") (pinfunction "2_2") (pintype "passive"))
      (node (ref "C62") (pin "2") (pinfunction "2_2") (pintype "passive"))
      (node (ref "JP3") (pin "1") (pinfunction "1_1") (pintype "passive"))
      (node (ref "R16") (pin "1") (pinfunction "1_1") (pintype "passive"))
      (node (ref "R17") (pin "1") (pinfunction "1_1") (pintype "passive"))
      (node (ref "R20") (pin "1") (pinfunction "1_1") (pintype "passive"))
      (node (ref "R21") (pin "1") (pinfunction "1_1") (pintype "passive"))
      (node (ref "U6") (pin "14") (pinfunction "VCC33_14") (pintype "passive"))
      (node (ref "U6") (pin "39") (pinfunction "VCC33_39") (pintype "passive"))
      (node (ref "U6") (pin "46") (pinfunction "MODE0_46") (pintype "passive"))
      (node (ref "U6") (pin "7") (pinfunction "VCC33_7") (pintype "passive"))
      (node (ref "U7") (pin "8") (pinfunction "VCC_8") (pintype "passive"))
    )
    (net (code "78") (name "VCC3V3-C") (class "Default")
      (node (ref "C70") (pin "2") (pinfunction "2_2") (pintype "passive"))
      (node (ref "C81") (pin "2") (pinfunction "2_2") (pintype "passive"))
      (node (ref "C82") (pin "2") (pinfunction "2_2") (pintype "passive"))
      (node (ref "C83") (pin "2") (pinfunction "2_2") (pintype "passive"))
      (node (ref "C84") (pin "2") (pinfunction "2_2") (pintype "passive"))
      (node (ref "JP4") (pin "1") (pinfunction "1_1") (pintype "passive"))
      (node (ref "R22") (pin "1") (pinfunction "1_1") (pintype "passive"))
      (node (ref "R23") (pin "1") (pinfunction "1_1") (pintype "passive"))
      (node (ref "R26") (pin "1") (pinfunction "1_1") (pintype "passive"))
      (node (ref "R27") (pin "2") (pinfunction "2_2") (pintype "passive"))
      (node (ref "U8") (pin "14") (pinfunction "VCC33_14") (pintype "passive"))
      (node (ref "U8") (pin "39") (pinfunction "VCC33_39") (pintype "passive"))
      (node (ref "U8") (pin "46") (pinfunction "MODE0_46") (pintype "passive"))
      (node (ref "U8") (pin "7") (pinfunction "VCC33_7") (pintype "passive"))
      (node (ref "U9") (pin "8") (pinfunction "VCC_8") (pintype "passive"))
    )
    (net (code "79") (name "unconnected-(U6-GPIO7-Pad41)") (class "Default")
      (node (ref "U6") (pin "41") (pinfunction "GPIO7_41") (pintype "passive+no_connect"))
    )
    (net (code "80") (name "unconnected-(U6-GPIO9-Pad48)") (class "Default")
      (node (ref "U6") (pin "48") (pinfunction "GPIO9_48") (pintype "passive+no_connect"))
    )
    (net (code "81") (name "unconnected-(U6-NC-Pad16)") (class "Default")
      (node (ref "U6") (pin "16") (pinfunction "NC_16") (pintype "passive+no_connect"))
    )
    (net (code "82") (name "unconnected-(U6-NC-Pad17)") (class "Default")
      (node (ref "U6") (pin "17") (pinfunction "NC_17") (pintype "passive+no_connect"))
    )
    (net (code "83") (name "unconnected-(U6-NC-Pad25)") (class "Default")
      (node (ref "U6") (pin "25") (pinfunction "NC_25") (pintype "passive+no_connect"))
    )
    (net (code "84") (name "unconnected-(U6-NC-Pad35)") (class "Default")
      (node (ref "U6") (pin "35") (pinfunction "NC_35") (pintype "passive+no_connect"))
    )
    (net (code "85") (name "unconnected-(U8-GPIO7-Pad41)") (class "Default")
      (node (ref "U8") (pin "41") (pinfunction "GPIO7_41") (pintype "passive+no_connect"))
    )
    (net (code "86") (name "unconnected-(U8-GPIO9-Pad48)") (class "Default")
      (node (ref "U8") (pin "48") (pinfunction "GPIO9_48") (pintype "passive+no_connect"))
    )
    (net (code "87") (name "unconnected-(U8-NC-Pad16)") (class "Default")
      (node (ref "U8") (pin "16") (pinfunction "NC_16") (pintype "passive+no_connect"))
    )
    (net (code "88") (name "unconnected-(U8-NC-Pad17)") (class "Default")
      (node (ref "U8") (pin "17") (pinfunction "NC_17") (pintype "passive+no_connect"))
    )
    (net (code "89") (name "unconnected-(U8-NC-Pad25)") (class "Default")
      (node (ref "U8") (pin "25") (pinfunction "NC_25") (pintype "passive+no_connect"))
    )
    (net (code "90") (name "unconnected-(U8-NC-Pad35)") (class "Default")
      (node (ref "U8") (pin "35") (pinfunction "NC_35") (pintype "passive+no_connect"))
    )
  )
)
